# OBDIIBoard_MCP2551.net
KiCad netlist of a schematic drawn in Altium Designer
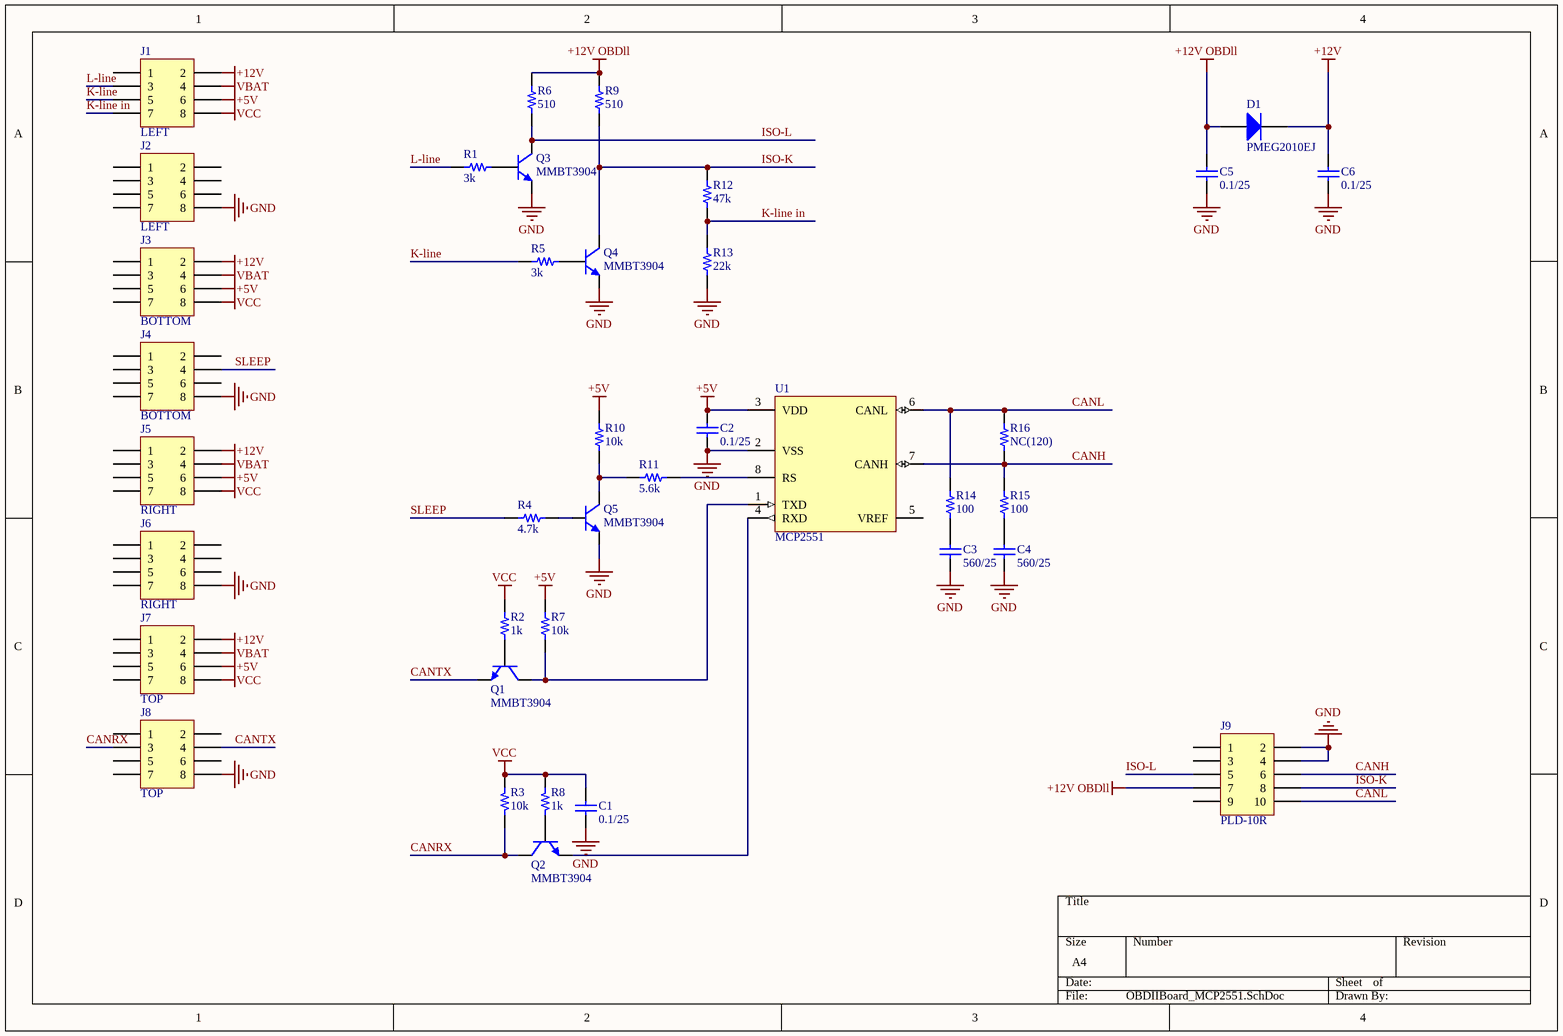
[diagram p0: OBDIIBoard_MCP2551.SchDoc]

(export (version "E")
  (design (tool "Eeschema 10.0.6"))
  (components
    (comp (ref "C1")
      (value "0.1/25")
      (footprint "CAP0402")
      (description "Ceramic chip capacitor 0402")
      (fields
        (field (name "PARTNUMBER") "CAP0402")
        (field (name "VOLTAGE") "25")
        (field (name "AUTHOR") "oiezhov")
      )
      (libsource (lib "Library") (part "Capacitor"))
    )
    (comp (ref "C2")
      (value "0.1/25")
      (footprint "CAP0402")
      (description "Ceramic chip capacitor 0402")
      (fields
        (field (name "PARTNUMBER") "CAP0402")
        (field (name "VOLTAGE") "25")
        (field (name "AUTHOR") "oiezhov")
      )
      (libsource (lib "Library") (part "Capacitor"))
    )
    (comp (ref "C3")
      (value "560/25")
      (footprint "CAP0402")
      (description "Ceramic chip capacitor 0402")
      (fields
        (field (name "PARTNUMBER") "CAP0402")
        (field (name "VOLTAGE") "25")
        (field (name "AUTHOR") "oiezhov")
      )
      (libsource (lib "Library") (part "Capacitor"))
    )
    (comp (ref "C4")
      (value "560/25")
      (footprint "CAP0402")
      (description "Ceramic chip capacitor 0402")
      (fields
        (field (name "PARTNUMBER") "CAP0402")
        (field (name "VOLTAGE") "25")
        (field (name "AUTHOR") "oiezhov")
      )
      (libsource (lib "Library") (part "Capacitor"))
    )
    (comp (ref "C5")
      (value "0.1/25")
      (footprint "CAP0402")
      (description "Ceramic chip capacitor 0402")
      (fields
        (field (name "PARTNUMBER") "CAP0402")
        (field (name "VOLTAGE") "25")
        (field (name "AUTHOR") "oiezhov")
      )
      (libsource (lib "Library") (part "Capacitor"))
    )
    (comp (ref "C6")
      (value "0.1/25")
      (footprint "CAP0402")
      (description "Ceramic chip capacitor 0402")
      (fields
        (field (name "PARTNUMBER") "CAP0402")
        (field (name "VOLTAGE") "25")
        (field (name "AUTHOR") "oiezhov")
      )
      (libsource (lib "Library") (part "Capacitor"))
    )
    (comp (ref "D1")
      (value "PMEG2010EJ")
      (footprint "SOD523")
      (description "1 A very low VF MEGA Schottky barrier rectifiers")
      (fields (field (name "AUTHOR") "oiezhov"))
      (libsource (lib "Library") (part "Diode"))
    )
    (comp (ref "J1")
      (value "LEFT")
      (footprint "PBDM-8")
      (description "2x4-pin header, pitch 2.54 mm")
      (fields (field (name "PARTNUMBER") "PBDM-8") (field (name "AUTHOR") "oiezhov"))
      (libsource (lib "Library") (part "8-pin dual row connector"))
    )
    (comp (ref "J2")
      (value "LEFT")
      (footprint "PBDM-8")
      (description "2x4-pin header, pitch 2.54 mm")
      (fields (field (name "PARTNUMBER") "PBDM-8") (field (name "AUTHOR") "oiezhov"))
      (libsource (lib "Library") (part "8-pin dual row connector"))
    )
    (comp (ref "J3")
      (value "BOTTOM")
      (footprint "PBDM-8")
      (description "2x4-pin header, pitch 2.54 mm")
      (fields (field (name "PARTNUMBER") "PBDM-8") (field (name "AUTHOR") "oiezhov"))
      (libsource (lib "Library") (part "8-pin dual row connector"))
    )
    (comp (ref "J4")
      (value "BOTTOM")
      (footprint "PBDM-8")
      (description "2x4-pin header, pitch 2.54 mm")
      (fields (field (name "PARTNUMBER") "PBDM-8") (field (name "AUTHOR") "oiezhov"))
      (libsource (lib "Library") (part "8-pin dual row connector"))
    )
    (comp (ref "J5")
      (value "RIGHT")
      (footprint "PBDM-8")
      (description "2x4-pin header, pitch 2.54 mm")
      (fields (field (name "PARTNUMBER") "PBDM-8") (field (name "AUTHOR") "oiezhov"))
      (libsource (lib "Library") (part "8-pin dual row connector"))
    )
    (comp (ref "J6")
      (value "RIGHT")
      (footprint "PBDM-8")
      (description "2x4-pin header, pitch 2.54 mm")
      (fields (field (name "PARTNUMBER") "PBDM-8") (field (name "AUTHOR") "oiezhov"))
      (libsource (lib "Library") (part "8-pin dual row connector"))
    )
    (comp (ref "J7")
      (value "TOP")
      (footprint "PBDM-8")
      (description "2x4-pin header, pitch 2.54 mm")
      (fields (field (name "PARTNUMBER") "PBDM-8") (field (name "AUTHOR") "oiezhov"))
      (libsource (lib "Library") (part "8-pin dual row connector"))
    )
    (comp (ref "J8")
      (value "TOP")
      (footprint "PBDM-8")
      (description "2x4-pin header, pitch 2.54 mm")
      (fields (field (name "PARTNUMBER") "PBDM-8") (field (name "AUTHOR") "oiezhov"))
      (libsource (lib "Library") (part "8-pin dual row connector"))
    )
    (comp (ref "J9")
      (value "PLD-10R")
      (footprint "PLD-10R")
      (description "Angle 2x5-pin header, pitch 2.54 mm")
      (fields (field (name "AUTHOR") "oiezhov"))
      (libsource (lib "Library") (part "10-pin dual row connector"))
    )
    (comp (ref "Q1")
      (value "MMBT3904")
      (footprint "SOT23")
      (description "NPN General Purpose Transistor")
      (fields (field (name "AUTHOR") "oiezhov"))
      (libsource (lib "Library") (part "NPN Transistor (B-E-C)"))
    )
    (comp (ref "Q2")
      (value "MMBT3904")
      (footprint "SOT23")
      (description "NPN General Purpose Transistor")
      (fields (field (name "AUTHOR") "oiezhov"))
      (libsource (lib "Library") (part "NPN Transistor (B-E-C)"))
    )
    (comp (ref "Q3")
      (value "MMBT3904")
      (footprint "SOT23")
      (description "NPN General Purpose Transistor")
      (fields (field (name "AUTHOR") "oiezhov"))
      (libsource (lib "Library") (part "NPN Transistor (B-E-C)"))
    )
    (comp (ref "Q4")
      (value "MMBT3904")
      (footprint "SOT23")
      (description "NPN General Purpose Transistor")
      (fields (field (name "AUTHOR") "oiezhov"))
      (libsource (lib "Library") (part "NPN Transistor (B-E-C)"))
    )
    (comp (ref "Q5")
      (value "MMBT3904")
      (footprint "SOT23")
      (description "NPN General Purpose Transistor")
      (fields (field (name "AUTHOR") "oiezhov"))
      (libsource (lib "Library") (part "NPN Transistor (B-E-C)"))
    )
    (comp (ref "R1")
      (value "3k")
      (footprint "RES0402")
      (description "Ceramic chip resistor")
      (fields (field (name "PARTNUMBER") "RES0402") (field (name "AUTHOR") "oiezhov"))
      (libsource (lib "Library") (part "Resistor"))
    )
    (comp (ref "R2")
      (value "1k")
      (footprint "RES0402")
      (description "Ceramic chip resistor")
      (fields (field (name "PARTNUMBER") "RES0402") (field (name "AUTHOR") "oiezhov"))
      (libsource (lib "Library") (part "Resistor"))
    )
    (comp (ref "R3")
      (value "10k")
      (footprint "RES0402")
      (description "Ceramic chip resistor")
      (fields (field (name "PARTNUMBER") "RES0402") (field (name "AUTHOR") "oiezhov"))
      (libsource (lib "Library") (part "Resistor"))
    )
    (comp (ref "R4")
      (value "4.7k")
      (footprint "RES0402")
      (description "Ceramic chip resistor")
      (fields (field (name "PARTNUMBER") "RES0402") (field (name "AUTHOR") "oiezhov"))
      (libsource (lib "Library") (part "Resistor"))
    )
    (comp (ref "R5")
      (value "3k")
      (footprint "RES0402")
      (description "Ceramic chip resistor")
      (fields (field (name "PARTNUMBER") "RES0402") (field (name "AUTHOR") "oiezhov"))
      (libsource (lib "Library") (part "Resistor"))
    )
    (comp (ref "R6")
      (value "510")
      (footprint "RES2512")
      (description "Ceramic chip resistor")
      (fields (field (name "PARTNUMBER") "RES2512") (field (name "AUTHOR") "oiezhov"))
      (libsource (lib "Library") (part "Resistor"))
    )
    (comp (ref "R7")
      (value "10k")
      (footprint "RES0402")
      (description "Ceramic chip resistor")
      (fields (field (name "PARTNUMBER") "RES0402") (field (name "AUTHOR") "oiezhov"))
      (libsource (lib "Library") (part "Resistor"))
    )
    (comp (ref "R8")
      (value "1k")
      (footprint "RES0402")
      (description "Ceramic chip resistor")
      (fields (field (name "PARTNUMBER") "RES0402") (field (name "AUTHOR") "oiezhov"))
      (libsource (lib "Library") (part "Resistor"))
    )
    (comp (ref "R9")
      (value "510")
      (footprint "RES2512")
      (description "Ceramic chip resistor")
      (fields (field (name "PARTNUMBER") "RES2512") (field (name "AUTHOR") "oiezhov"))
      (libsource (lib "Library") (part "Resistor"))
    )
    (comp (ref "R10")
      (value "10k")
      (footprint "RES0402")
      (description "Ceramic chip resistor")
      (fields (field (name "PARTNUMBER") "RES0402") (field (name "AUTHOR") "oiezhov"))
      (libsource (lib "Library") (part "Resistor"))
    )
    (comp (ref "R11")
      (value "5.6k")
      (footprint "RES0402")
      (description "Ceramic chip resistor")
      (fields (field (name "PARTNUMBER") "RES0402") (field (name "AUTHOR") "oiezhov"))
      (libsource (lib "Library") (part "Resistor"))
    )
    (comp (ref "R12")
      (value "47k")
      (footprint "RES0402")
      (description "Ceramic chip resistor")
      (fields (field (name "PARTNUMBER") "RES0402") (field (name "AUTHOR") "oiezhov"))
      (libsource (lib "Library") (part "Resistor"))
    )
    (comp (ref "R13")
      (value "22k")
      (footprint "RES0402")
      (description "Ceramic chip resistor")
      (fields (field (name "PARTNUMBER") "RES0402") (field (name "AUTHOR") "oiezhov"))
      (libsource (lib "Library") (part "Resistor"))
    )
    (comp (ref "R14")
      (value "100")
      (footprint "RES0402")
      (description "Ceramic chip resistor")
      (fields (field (name "PARTNUMBER") "RES0402") (field (name "AUTHOR") "oiezhov"))
      (libsource (lib "Library") (part "Resistor"))
    )
    (comp (ref "R15")
      (value "100")
      (footprint "RES0402")
      (description "Ceramic chip resistor")
      (fields (field (name "PARTNUMBER") "RES0402") (field (name "AUTHOR") "oiezhov"))
      (libsource (lib "Library") (part "Resistor"))
    )
    (comp (ref "R16")
      (value "NC(120)")
      (footprint "RES0402")
      (description "Ceramic chip resistor")
      (fields (field (name "PARTNUMBER") "RES0402") (field (name "AUTHOR") "oiezhov"))
      (libsource (lib "Library") (part "Resistor"))
    )
    (comp (ref "U1")
      (value "MCP2551")
      (footprint "SO8")
      (description "High-Speed CAN Transceiver")
      (libsource (lib "Library") (part "MCP2551"))
    )
  )
  (nets
    (net (code "1") (name "+5V") (class "Default")
      (node (ref "C2") (pin "2") (pinfunction "2_2") (pintype "passive"))
      (node (ref "J1") (pin "6") (pinfunction "6_6") (pintype "passive"))
      (node (ref "J3") (pin "6") (pinfunction "6_6") (pintype "passive"))
      (node (ref "J5") (pin "6") (pinfunction "6_6") (pintype "passive"))
      (node (ref "J7") (pin "6") (pinfunction "6_6") (pintype "passive"))
      (node (ref "R10") (pin "2") (pinfunction "2_2") (pintype "passive"))
      (node (ref "R7") (pin "1") (pinfunction "1_1") (pintype "passive"))
      (node (ref "U1") (pin "3") (pinfunction "VDD_3") (pintype "power_in"))
    )
    (net (code "2") (name "+12V") (class "Default")
      (node (ref "C6") (pin "2") (pinfunction "2_2") (pintype "passive"))
      (node (ref "D1") (pin "1") (pinfunction "1_1") (pintype "passive"))
      (node (ref "J1") (pin "2") (pinfunction "2_2") (pintype "passive"))
      (node (ref "J3") (pin "2") (pinfunction "2_2") (pintype "passive"))
      (node (ref "J5") (pin "2") (pinfunction "2_2") (pintype "passive"))
      (node (ref "J7") (pin "2") (pinfunction "2_2") (pintype "passive"))
    )
    (net (code "3") (name "+12V OBDll") (class "Default")
      (node (ref "C5") (pin "2") (pinfunction "2_2") (pintype "passive"))
      (node (ref "D1") (pin "2") (pinfunction "2_2") (pintype "passive"))
      (node (ref "J9") (pin "7") (pinfunction "7_7") (pintype "passive"))
      (node (ref "R6") (pin "2") (pinfunction "2_2") (pintype "passive"))
      (node (ref "R9") (pin "2") (pinfunction "2_2") (pintype "passive"))
    )
    (net (code "4") (name "/CANH") (class "Default")
      (node (ref "J9") (pin "6") (pinfunction "6_6") (pintype "passive"))
      (node (ref "R15") (pin "2") (pinfunction "2_2") (pintype "passive"))
      (node (ref "R16") (pin "1") (pinfunction "1_1") (pintype "passive"))
      (node (ref "U1") (pin "7") (pinfunction "CANH_7") (pintype "bidirectional"))
    )
    (net (code "5") (name "/CANL") (class "Default")
      (node (ref "J9") (pin "10") (pinfunction "10_10") (pintype "passive"))
      (node (ref "R14") (pin "2") (pinfunction "2_2") (pintype "passive"))
      (node (ref "R16") (pin "2") (pinfunction "2_2") (pintype "passive"))
      (node (ref "U1") (pin "6") (pinfunction "CANL_6") (pintype "bidirectional"))
    )
    (net (code "6") (name "/CANRX") (class "Default")
      (node (ref "J8") (pin "3") (pinfunction "3_3") (pintype "passive"))
      (node (ref "Q2") (pin "3") (pinfunction "3_3") (pintype "passive"))
      (node (ref "R3") (pin "2") (pinfunction "2_2") (pintype "passive"))
    )
    (net (code "7") (name "/CANTX") (class "Default")
      (node (ref "J8") (pin "4") (pinfunction "4_4") (pintype "passive"))
      (node (ref "Q1") (pin "2") (pinfunction "2_2") (pintype "passive"))
    )
    (net (code "8") (name "/ISO-K") (class "Default")
      (node (ref "J9") (pin "8") (pinfunction "8_8") (pintype "passive"))
      (node (ref "Q4") (pin "3") (pinfunction "3_3") (pintype "passive"))
      (node (ref "R12") (pin "1") (pinfunction "1_1") (pintype "passive"))
      (node (ref "R9") (pin "1") (pinfunction "1_1") (pintype "passive"))
    )
    (net (code "9") (name "/ISO-L") (class "Default")
      (node (ref "J9") (pin "5") (pinfunction "5_5") (pintype "passive"))
      (node (ref "Q3") (pin "3") (pinfunction "3_3") (pintype "passive"))
      (node (ref "R6") (pin "1") (pinfunction "1_1") (pintype "passive"))
    )
    (net (code "10") (name "/K-line") (class "Default")
      (node (ref "J1") (pin "5") (pinfunction "5_5") (pintype "passive"))
      (node (ref "R5") (pin "2") (pinfunction "2_2") (pintype "passive"))
    )
    (net (code "11") (name "/K-line in") (class "Default")
      (node (ref "J1") (pin "7") (pinfunction "7_7") (pintype "passive"))
      (node (ref "R12") (pin "2") (pinfunction "2_2") (pintype "passive"))
      (node (ref "R13") (pin "1") (pinfunction "1_1") (pintype "passive"))
    )
    (net (code "12") (name "/L-line") (class "Default")
      (node (ref "J1") (pin "3") (pinfunction "3_3") (pintype "passive"))
      (node (ref "R1") (pin "2") (pinfunction "2_2") (pintype "passive"))
    )
    (net (code "13") (name "/SLEEP") (class "Default")
      (node (ref "J4") (pin "4") (pinfunction "4_4") (pintype "passive"))
      (node (ref "R4") (pin "2") (pinfunction "2_2") (pintype "passive"))
    )
    (net (code "14") (name "GND") (class "Default")
      (node (ref "C1") (pin "1") (pinfunction "1_1") (pintype "passive"))
      (node (ref "C2") (pin "1") (pinfunction "1_1") (pintype "passive"))
      (node (ref "C3") (pin "1") (pinfunction "1_1") (pintype "passive"))
      (node (ref "C4") (pin "1") (pinfunction "1_1") (pintype "passive"))
      (node (ref "C5") (pin "1") (pinfunction "1_1") (pintype "passive"))
      (node (ref "C6") (pin "1") (pinfunction "1_1") (pintype "passive"))
      (node (ref "J2") (pin "8") (pinfunction "8_8") (pintype "passive"))
      (node (ref "J4") (pin "8") (pinfunction "8_8") (pintype "passive"))
      (node (ref "J6") (pin "8") (pinfunction "8_8") (pintype "passive"))
      (node (ref "J8") (pin "8") (pinfunction "8_8") (pintype "passive"))
      (node (ref "J9") (pin "2") (pinfunction "2_2") (pintype "passive"))
      (node (ref "J9") (pin "4") (pinfunction "4_4") (pintype "passive"))
      (node (ref "Q3") (pin "2") (pinfunction "2_2") (pintype "passive"))
      (node (ref "Q4") (pin "2") (pinfunction "2_2") (pintype "passive"))
      (node (ref "Q5") (pin "2") (pinfunction "2_2") (pintype "passive"))
      (node (ref "R13") (pin "2") (pinfunction "2_2") (pintype "passive"))
      (node (ref "U1") (pin "2") (pinfunction "VSS_2") (pintype "power_in"))
    )
    (net (code "15") (name "Net-(C3-Pad2)") (class "Default")
      (node (ref "C3") (pin "2") (pinfunction "2_2") (pintype "passive"))
      (node (ref "R14") (pin "1") (pinfunction "1_1") (pintype "passive"))
    )
    (net (code "16") (name "Net-(C4-Pad2)") (class "Default")
      (node (ref "C4") (pin "2") (pinfunction "2_2") (pintype "passive"))
      (node (ref "R15") (pin "1") (pinfunction "1_1") (pintype "passive"))
    )
    (net (code "17") (name "Net-(Q1-Pad1)") (class "Default")
      (node (ref "Q1") (pin "1") (pinfunction "1_1") (pintype "passive"))
      (node (ref "R2") (pin "2") (pinfunction "2_2") (pintype "passive"))
    )
    (net (code "18") (name "Net-(Q2-Pad1)") (class "Default")
      (node (ref "Q2") (pin "1") (pinfunction "1_1") (pintype "passive"))
      (node (ref "R8") (pin "2") (pinfunction "2_2") (pintype "passive"))
    )
    (net (code "19") (name "Net-(Q3-Pad1)") (class "Default")
      (node (ref "Q3") (pin "1") (pinfunction "1_1") (pintype "passive"))
      (node (ref "R1") (pin "1") (pinfunction "1_1") (pintype "passive"))
    )
    (net (code "20") (name "Net-(Q4-Pad1)") (class "Default")
      (node (ref "Q4") (pin "1") (pinfunction "1_1") (pintype "passive"))
      (node (ref "R5") (pin "1") (pinfunction "1_1") (pintype "passive"))
    )
    (net (code "21") (name "Net-(Q5-Pad1)") (class "Default")
      (node (ref "Q5") (pin "1") (pinfunction "1_1") (pintype "passive"))
      (node (ref "R4") (pin "1") (pinfunction "1_1") (pintype "passive"))
    )
    (net (code "22") (name "Net-(Q5-Pad3)") (class "Default")
      (node (ref "Q5") (pin "3") (pinfunction "3_3") (pintype "passive"))
      (node (ref "R10") (pin "1") (pinfunction "1_1") (pintype "passive"))
      (node (ref "R11") (pin "2") (pinfunction "2_2") (pintype "passive"))
    )
    (net (code "23") (name "Net-(U1-RS)") (class "Default")
      (node (ref "R11") (pin "1") (pinfunction "1_1") (pintype "passive"))
      (node (ref "U1") (pin "8") (pinfunction "RS_8") (pintype "passive"))
    )
    (net (code "24") (name "Net-(U1-RXD)") (class "Default")
      (node (ref "Q2") (pin "2") (pinfunction "2_2") (pintype "passive"))
      (node (ref "U1") (pin "4") (pinfunction "RXD_4") (pintype "output"))
    )
    (net (code "25") (name "Net-(U1-TXD)") (class "Default")
      (node (ref "Q1") (pin "3") (pinfunction "3_3") (pintype "passive"))
      (node (ref "R7") (pin "2") (pinfunction "2_2") (pintype "passive"))
      (node (ref "U1") (pin "1") (pinfunction "TXD_1") (pintype "input"))
    )
    (net (code "26") (name "VBAT") (class "Default")
      (node (ref "J1") (pin "4") (pinfunction "4_4") (pintype "passive"))
      (node (ref "J3") (pin "4") (pinfunction "4_4") (pintype "passive"))
      (node (ref "J5") (pin "4") (pinfunction "4_4") (pintype "passive"))
      (node (ref "J7") (pin "4") (pinfunction "4_4") (pintype "passive"))
    )
    (net (code "27") (name "VCC") (class "Default")
      (node (ref "C1") (pin "2") (pinfunction "2_2") (pintype "passive"))
      (node (ref "J1") (pin "8") (pinfunction "8_8") (pintype "passive"))
      (node (ref "J3") (pin "8") (pinfunction "8_8") (pintype "passive"))
      (node (ref "J5") (pin "8") (pinfunction "8_8") (pintype "passive"))
      (node (ref "J7") (pin "8") (pinfunction "8_8") (pintype "passive"))
      (node (ref "R2") (pin "1") (pinfunction "1_1") (pintype "passive"))
      (node (ref "R3") (pin "1") (pinfunction "1_1") (pintype "passive"))
      (node (ref "R8") (pin "1") (pinfunction "1_1") (pintype "passive"))
    )
    (net (code "28") (name "unconnected-(J1-Pad1)") (class "Default")
      (node (ref "J1") (pin "1") (pinfunction "1_1") (pintype "passive"))
    )
    (net (code "29") (name "unconnected-(J2-Pad1)") (class "Default")
      (node (ref "J2") (pin "1") (pinfunction "1_1") (pintype "passive"))
    )
    (net (code "30") (name "unconnected-(J2-Pad2)") (class "Default")
      (node (ref "J2") (pin "2") (pinfunction "2_2") (pintype "passive"))
    )
    (net (code "31") (name "unconnected-(J2-Pad3)") (class "Default")
      (node (ref "J2") (pin "3") (pinfunction "3_3") (pintype "passive"))
    )
    (net (code "32") (name "unconnected-(J2-Pad4)") (class "Default")
      (node (ref "J2") (pin "4") (pinfunction "4_4") (pintype "passive"))
    )
    (net (code "33") (name "unconnected-(J2-Pad5)") (class "Default")
      (node (ref "J2") (pin "5") (pinfunction "5_5") (pintype "passive"))
    )
    (net (code "34") (name "unconnected-(J2-Pad6)") (class "Default")
      (node (ref "J2") (pin "6") (pinfunction "6_6") (pintype "passive"))
    )
    (net (code "35") (name "unconnected-(J2-Pad7)") (class "Default")
      (node (ref "J2") (pin "7") (pinfunction "7_7") (pintype "passive"))
    )
    (net (code "36") (name "unconnected-(J3-Pad1)") (class "Default")
      (node (ref "J3") (pin "1") (pinfunction "1_1") (pintype "passive"))
    )
    (net (code "37") (name "unconnected-(J3-Pad3)") (class "Default")
      (node (ref "J3") (pin "3") (pinfunction "3_3") (pintype "passive"))
    )
    (net (code "38") (name "unconnected-(J3-Pad5)") (class "Default")
      (node (ref "J3") (pin "5") (pinfunction "5_5") (pintype "passive"))
    )
    (net (code "39") (name "unconnected-(J3-Pad7)") (class "Default")
      (node (ref "J3") (pin "7") (pinfunction "7_7") (pintype "passive"))
    )
    (net (code "40") (name "unconnected-(J4-Pad1)") (class "Default")
      (node (ref "J4") (pin "1") (pinfunction "1_1") (pintype "passive"))
    )
    (net (code "41") (name "unconnected-(J4-Pad2)") (class "Default")
      (node (ref "J4") (pin "2") (pinfunction "2_2") (pintype "passive"))
    )
    (net (code "42") (name "unconnected-(J4-Pad3)") (class "Default")
      (node (ref "J4") (pin "3") (pinfunction "3_3") (pintype "passive"))
    )
    (net (code "43") (name "unconnected-(J4-Pad5)") (class "Default")
      (node (ref "J4") (pin "5") (pinfunction "5_5") (pintype "passive"))
    )
    (net (code "44") (name "unconnected-(J4-Pad6)") (class "Default")
      (node (ref "J4") (pin "6") (pinfunction "6_6") (pintype "passive"))
    )
    (net (code "45") (name "unconnected-(J4-Pad7)") (class "Default")
      (node (ref "J4") (pin "7") (pinfunction "7_7") (pintype "passive"))
    )
    (net (code "46") (name "unconnected-(J5-Pad1)") (class "Default")
      (node (ref "J5") (pin "1") (pinfunction "1_1") (pintype "passive"))
    )
    (net (code "47") (name "unconnected-(J5-Pad3)") (class "Default")
      (node (ref "J5") (pin "3") (pinfunction "3_3") (pintype "passive"))
    )
    (net (code "48") (name "unconnected-(J5-Pad5)") (class "Default")
      (node (ref "J5") (pin "5") (pinfunction "5_5") (pintype "passive"))
    )
    (net (code "49") (name "unconnected-(J5-Pad7)") (class "Default")
      (node (ref "J5") (pin "7") (pinfunction "7_7") (pintype "passive"))
    )
    (net (code "50") (name "unconnected-(J6-Pad1)") (class "Default")
      (node (ref "J6") (pin "1") (pinfunction "1_1") (pintype "passive"))
    )
    (net (code "51") (name "unconnected-(J6-Pad2)") (class "Default")
      (node (ref "J6") (pin "2") (pinfunction "2_2") (pintype "passive"))
    )
    (net (code "52") (name "unconnected-(J6-Pad3)") (class "Default")
      (node (ref "J6") (pin "3") (pinfunction "3_3") (pintype "passive"))
    )
    (net (code "53") (name "unconnected-(J6-Pad4)") (class "Default")
      (node (ref "J6") (pin "4") (pinfunction "4_4") (pintype "passive"))
    )
    (net (code "54") (name "unconnected-(J6-Pad5)") (class "Default")
      (node (ref "J6") (pin "5") (pinfunction "5_5") (pintype "passive"))
    )
    (net (code "55") (name "unconnected-(J6-Pad6)") (class "Default")
      (node (ref "J6") (pin "6") (pinfunction "6_6") (pintype "passive"))
    )
    (net (code "56") (name "unconnected-(J6-Pad7)") (class "Default")
      (node (ref "J6") (pin "7") (pinfunction "7_7") (pintype "passive"))
    )
    (net (code "57") (name "unconnected-(J7-Pad1)") (class "Default")
      (node (ref "J7") (pin "1") (pinfunction "1_1") (pintype "passive"))
    )
    (net (code "58") (name "unconnected-(J7-Pad3)") (class "Default")
      (node (ref "J7") (pin "3") (pinfunction "3_3") (pintype "passive"))
    )
    (net (code "59") (name "unconnected-(J7-Pad5)") (class "Default")
      (node (ref "J7") (pin "5") (pinfunction "5_5") (pintype "passive"))
    )
    (net (code "60") (name "unconnected-(J7-Pad7)") (class "Default")
      (node (ref "J7") (pin "7") (pinfunction "7_7") (pintype "passive"))
    )
    (net (code "61") (name "unconnected-(J8-Pad1)") (class "Default")
      (node (ref "J8") (pin "1") (pinfunction "1_1") (pintype "passive"))
    )
    (net (code "62") (name "unconnected-(J8-Pad2)") (class "Default")
      (node (ref "J8") (pin "2") (pinfunction "2_2") (pintype "passive"))
    )
    (net (code "63") (name "unconnected-(J8-Pad5)") (class "Default")
      (node (ref "J8") (pin "5") (pinfunction "5_5") (pintype "passive"))
    )
    (net (code "64") (name "unconnected-(J8-Pad6)") (class "Default")
      (node (ref "J8") (pin "6") (pinfunction "6_6") (pintype "passive"))
    )
    (net (code "65") (name "unconnected-(J8-Pad7)") (class "Default")
      (node (ref "J8") (pin "7") (pinfunction "7_7") (pintype "passive"))
    )
    (net (code "66") (name "unconnected-(J9-Pad1)") (class "Default")
      (node (ref "J9") (pin "1") (pinfunction "1_1") (pintype "passive"))
    )
    (net (code "67") (name "unconnected-(J9-Pad3)") (class "Default")
      (node (ref "J9") (pin "3") (pinfunction "3_3") (pintype "passive"))
    )
    (net (code "68") (name "unconnected-(J9-Pad9)") (class "Default")
      (node (ref "J9") (pin "9") (pinfunction "9_9") (pintype "passive"))
    )
    (net (code "69") (name "unconnected-(U1-VREF-Pad5)") (class "Default")
      (node (ref "U1") (pin "5") (pinfunction "VREF_5") (pintype "passive"))
    )
  )
)
